# RoverWing-V1_5.net
KiCad netlist of a schematic drawn in EAGLE
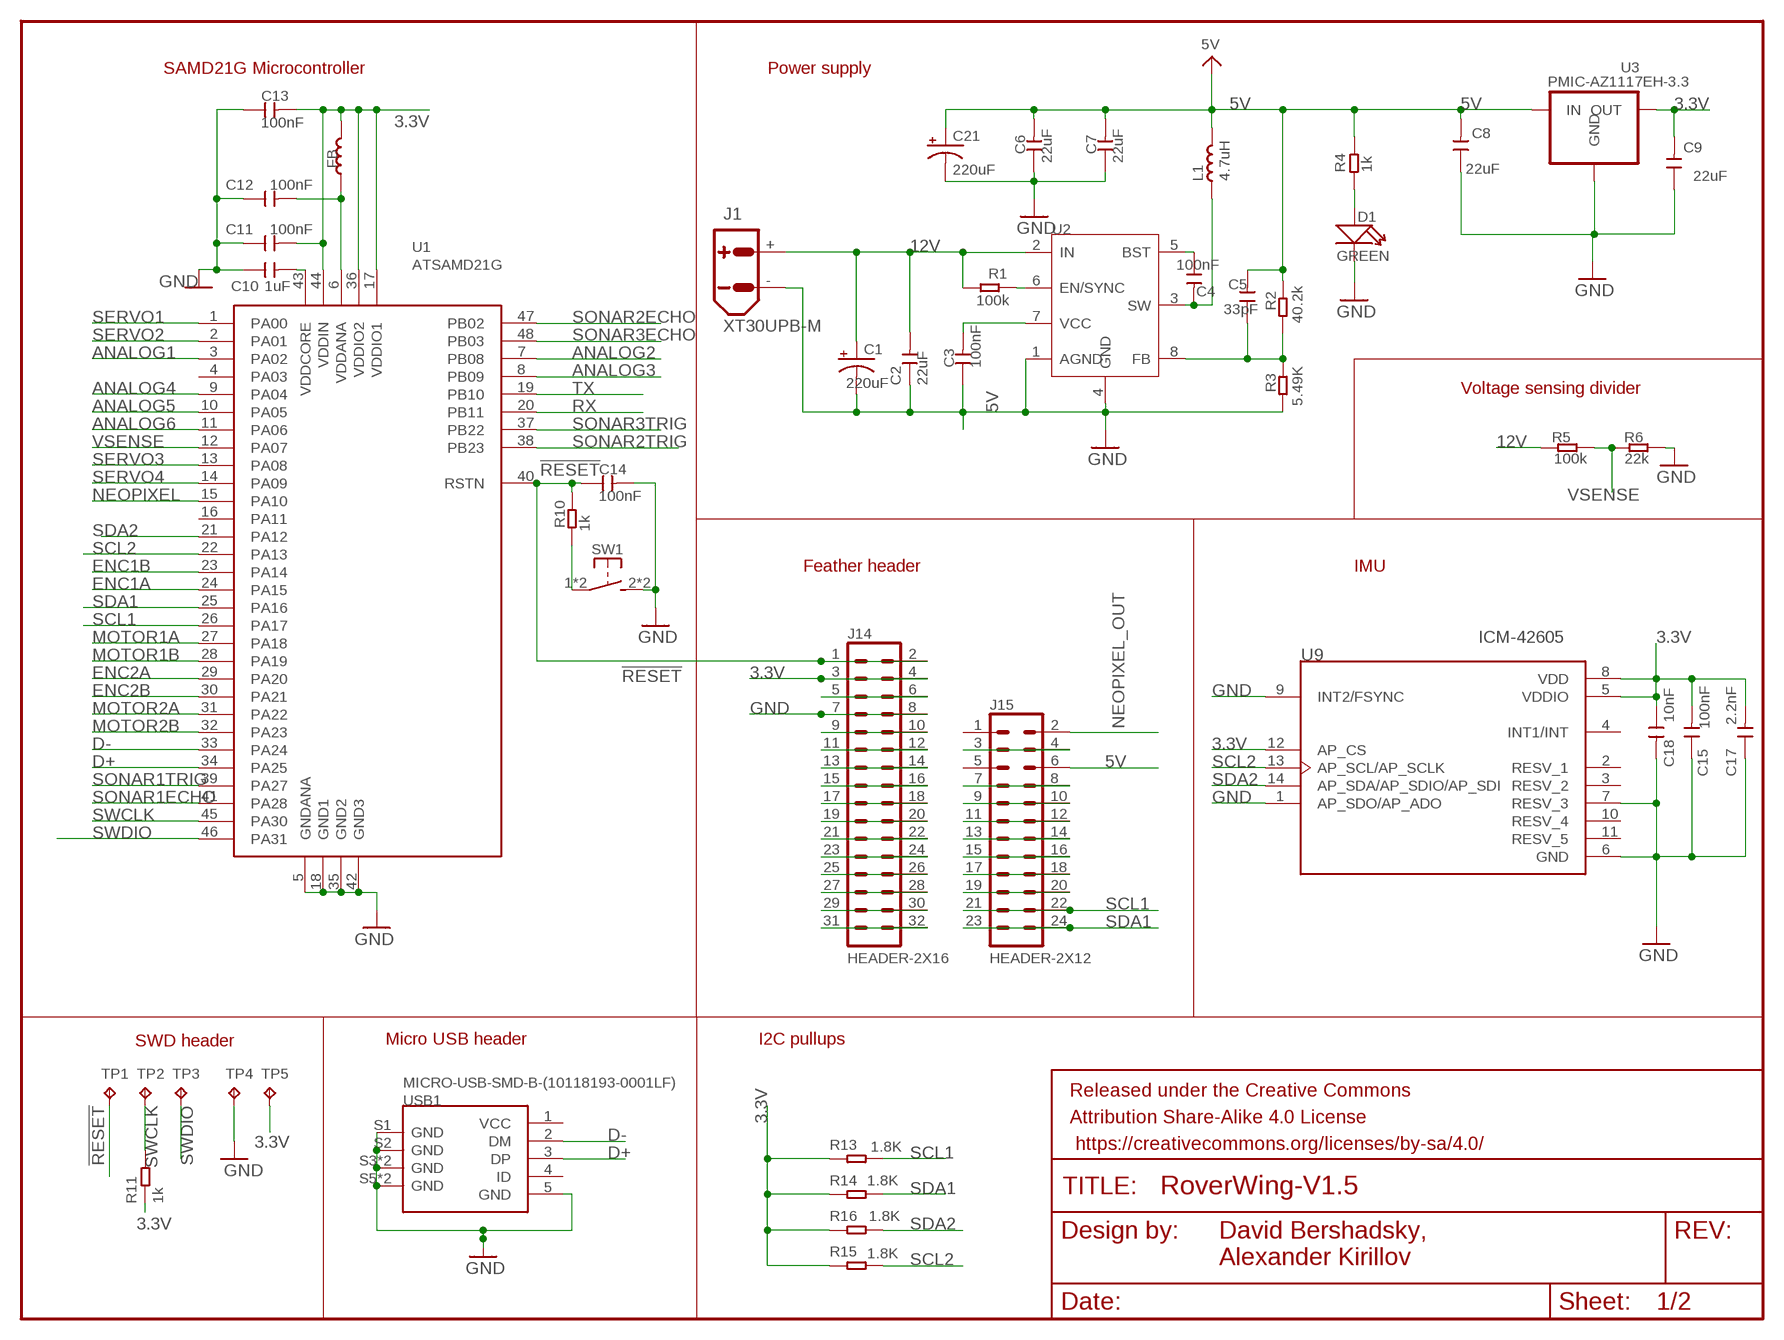
[diagram p0: schematic, sheet 1]
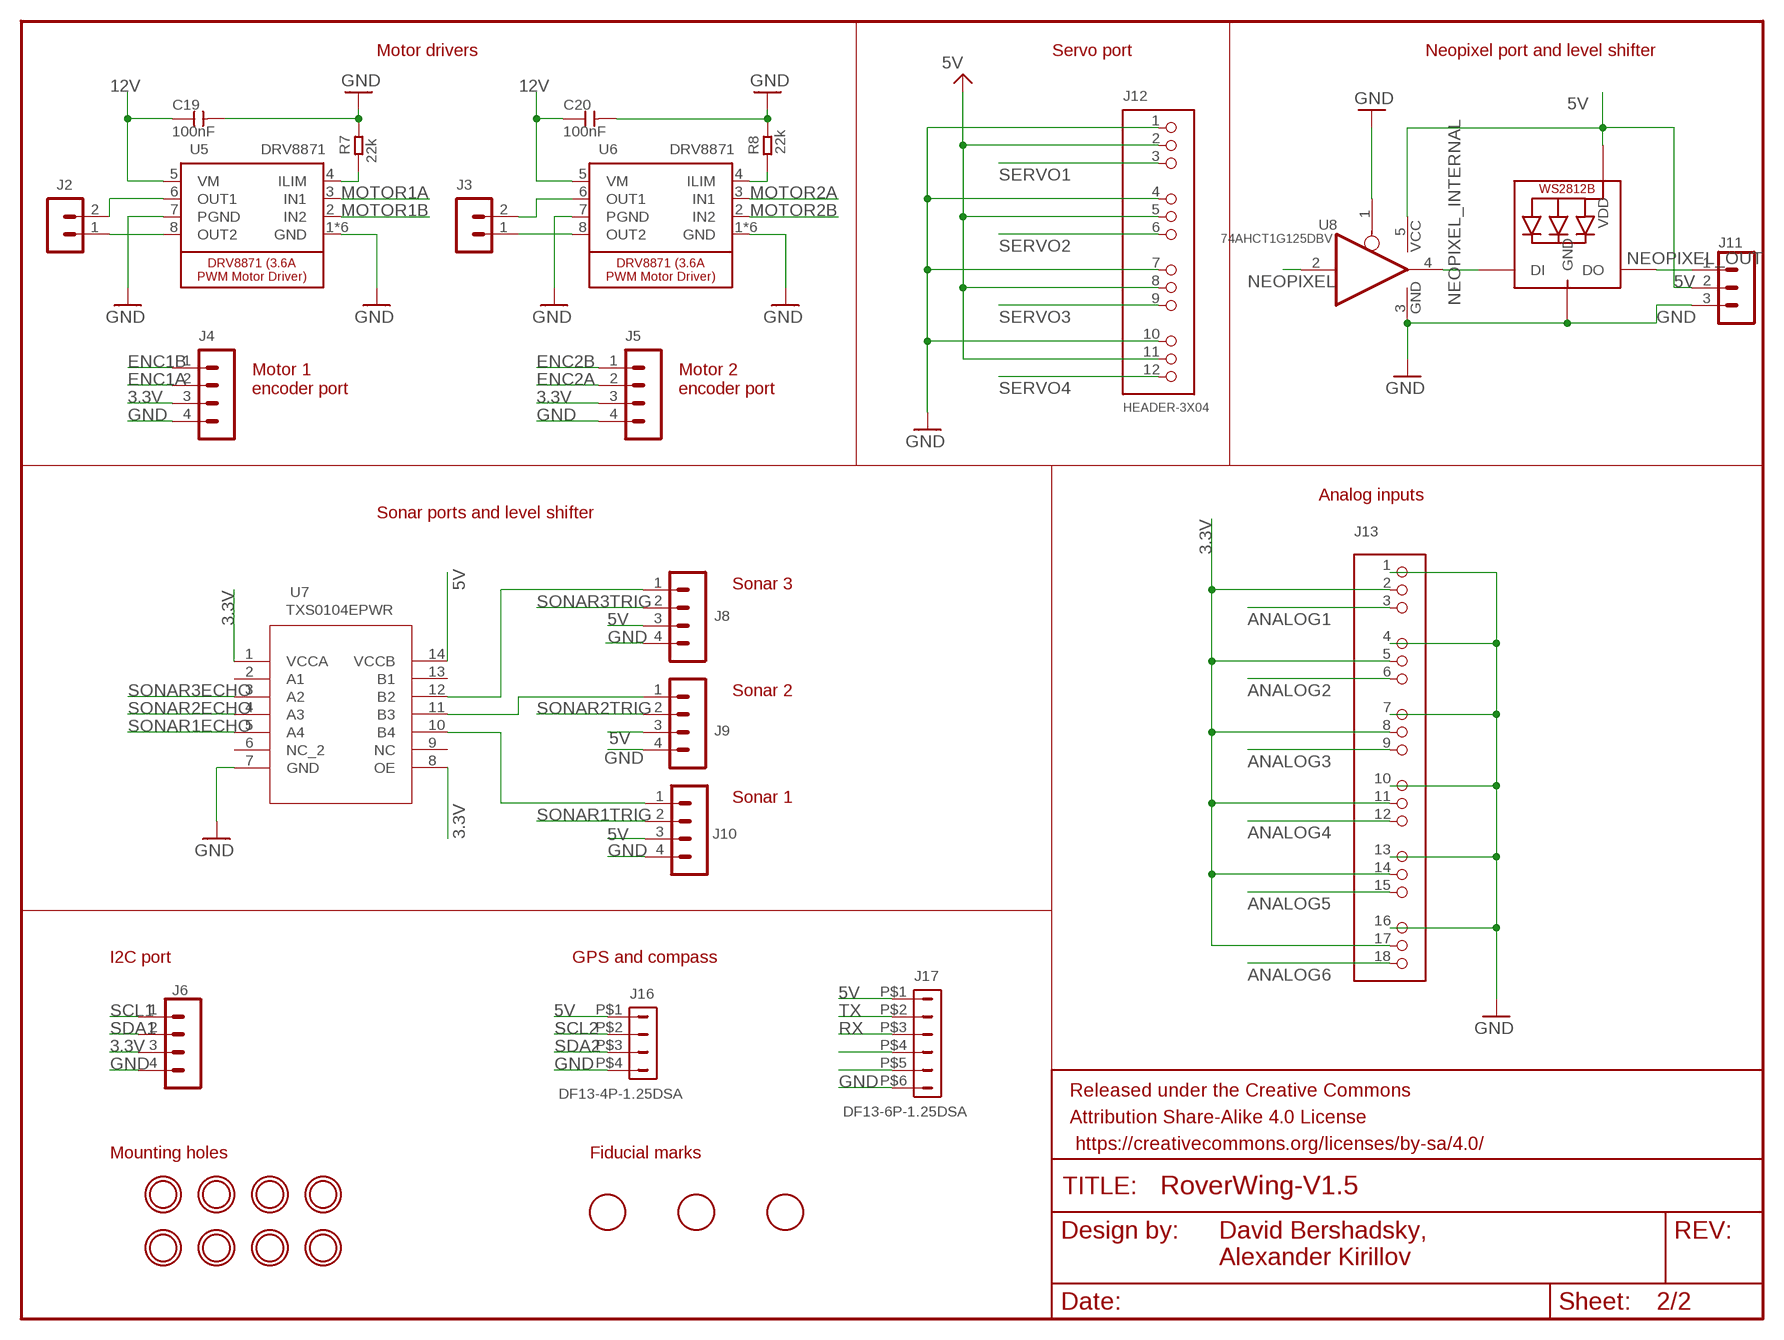
[diagram p1: schematic, sheet 2]

(export (version "E")
  (design (tool "Eeschema 10.0.6"))
  (components
    (comp (ref "C19")
      (value "100nF")
      (footprint "eagle-import:0805")
      (libsource (lib "eagle-import") (part "CAP-CERAMIC-SMD0805"))
    )
    (comp (ref "C20")
      (value "100nF")
      (footprint "eagle-import:0805")
      (libsource (lib "eagle-import") (part "CAP-CERAMIC-SMD0805"))
    )
    (comp (ref "D2")
      (value "WS2812B3535")
      (footprint "eagle-import:LED3535")
      (fields (field (name "MANUFACTURER") "Worldsemi") (field (name "PARTNO") "WS2812B-3535 "))
      (libsource (lib "eagle-import") (part "WS2812B3535"))
    )
    (comp (ref "FRAME1")
      (value "FRAME-LETTERNO_PACKAGE")
      (footprint "eagle-import:DUMMY")
      (libsource (lib "eagle-import") (part "FRAME-LETTERNO_PACKAGE"))
    )
    (comp (ref "J2")
      (value "HEADER-VH")
      (footprint "eagle-import:B2P-VH")
      (fields (field (name "PARTNO") "B2P-VH(LF)(SN)  "))
      (libsource (lib "eagle-import") (part "HEADER-VH"))
    )
    (comp (ref "J3")
      (value "HEADER-VH")
      (footprint "eagle-import:B2P-VH")
      (fields (field (name "PARTNO") "B2P-VH(LF)(SN)  "))
      (libsource (lib "eagle-import") (part "HEADER-VH"))
    )
    (comp (ref "J4")
      (value "HEADER-PH-4P")
      (footprint "eagle-import:B4B-PH-K")
      (fields (field (name "PARTNO") "B4B-PH-K-S(LF)(SN)"))
      (libsource (lib "eagle-import") (part "HEADER-PH-4P"))
    )
    (comp (ref "J5")
      (value "HEADER-PH-4P")
      (footprint "eagle-import:B4B-PH-K")
      (fields (field (name "PARTNO") "B4B-PH-K-S(LF)(SN)"))
      (libsource (lib "eagle-import") (part "HEADER-PH-4P"))
    )
    (comp (ref "J6")
      (value "HEADER-PH-4P")
      (footprint "eagle-import:B4B-PH-K")
      (fields (field (name "PARTNO") "B4B-PH-K-S(LF)(SN)"))
      (libsource (lib "eagle-import") (part "HEADER-PH-4P"))
    )
    (comp (ref "J8")
      (value "HEADER-PH-4P")
      (footprint "eagle-import:B4B-PH-K")
      (fields (field (name "PARTNO") "B4B-PH-K-S(LF)(SN)"))
      (libsource (lib "eagle-import") (part "HEADER-PH-4P"))
    )
    (comp (ref "J9")
      (value "HEADER-PH-4P")
      (footprint "eagle-import:B4B-PH-K")
      (fields (field (name "PARTNO") "B4B-PH-K-S(LF)(SN)"))
      (libsource (lib "eagle-import") (part "HEADER-PH-4P"))
    )
    (comp (ref "J10")
      (value "HEADER-PH-4P")
      (footprint "eagle-import:B4B-PH-K")
      (fields (field (name "PARTNO") "B4B-PH-K-S(LF)(SN)"))
      (libsource (lib "eagle-import") (part "HEADER-PH-4P"))
    )
    (comp (ref "J11")
      (value "HEADER-PH-3P")
      (footprint "eagle-import:B3B-PH-K")
      (fields (field (name "PARTNO") "B3B-PH-K-S(LF)(SN)"))
      (libsource (lib "eagle-import") (part "HEADER-PH-3P"))
    )
    (comp (ref "J12")
      (value "HEADER-3X04")
      (footprint "eagle-import:3X04")
      (libsource (lib "eagle-import") (part "HEADER-3X04"))
    )
    (comp (ref "J13")
      (value "HEADER-3X06\"")
      (footprint "eagle-import:3X06")
      (libsource (lib "eagle-import") (part "HEADER-3X06{dblquote}"))
    )
    (comp (ref "J16")
      (value "DF13-4P-1.25DSA")
      (footprint "eagle-import:DF13-4P-1.25DSA")
      (libsource (lib "eagle-import") (part "DF13-4P-1.25DSA"))
    )
    (comp (ref "J17")
      (value "DF13-6P-1.25DSA")
      (footprint "eagle-import:DF13-6P-1.25DSA")
      (libsource (lib "eagle-import") (part "DF13-6P-1.25DSA"))
    )
    (comp (ref "R7")
      (value "22k")
      (footprint "eagle-import:0805")
      (libsource (lib "eagle-import") (part "RES-SMD-0805"))
    )
    (comp (ref "R8")
      (value "22k")
      (footprint "eagle-import:0805")
      (libsource (lib "eagle-import") (part "RES-SMD-0805"))
    )
    (comp (ref "U$3")
      (value "MOUNTINGHOLE3.0_NPH")
      (footprint "eagle-import:MOUNTINGHOLE_3.0_NPH")
      (libsource (lib "eagle-import") (part "MOUNTINGHOLE3.0_NPH"))
    )
    (comp (ref "U$4")
      (value "MOUNTINGHOLE3.0_NPH")
      (footprint "eagle-import:MOUNTINGHOLE_3.0_NPH")
      (libsource (lib "eagle-import") (part "MOUNTINGHOLE3.0_NPH"))
    )
    (comp (ref "U$11")
      (value "FIDUCIAL")
      (footprint "eagle-import:FIDUCIAL_1MM")
      (libsource (lib "eagle-import") (part "FIDUCIAL"))
    )
    (comp (ref "U$13")
      (value "FIDUCIAL")
      (footprint "eagle-import:FIDUCIAL_1MM")
      (libsource (lib "eagle-import") (part "FIDUCIAL"))
    )
    (comp (ref "U$14")
      (value "MOUNTINGHOLE3.0_NPH")
      (footprint "eagle-import:MOUNTINGHOLE_3.0_NPH")
      (libsource (lib "eagle-import") (part "MOUNTINGHOLE3.0_NPH"))
    )
    (comp (ref "U$15")
      (value "MOUNTINGHOLE3.0_NPH")
      (footprint "eagle-import:MOUNTINGHOLE_3.0_NPH")
      (libsource (lib "eagle-import") (part "MOUNTINGHOLE3.0_NPH"))
    )
    (comp (ref "U$17")
      (value "FIDUCIAL")
      (footprint "eagle-import:FIDUCIAL_1MM")
      (libsource (lib "eagle-import") (part "FIDUCIAL"))
    )
    (comp (ref "U$24")
      (value "MOUNTINGHOLE3.0_NPH")
      (footprint "eagle-import:MOUNTINGHOLE_3.0_NPH")
      (libsource (lib "eagle-import") (part "MOUNTINGHOLE3.0_NPH"))
    )
    (comp (ref "U$25")
      (value "MOUNTINGHOLE3.0_NPH")
      (footprint "eagle-import:MOUNTINGHOLE_3.0_NPH")
      (libsource (lib "eagle-import") (part "MOUNTINGHOLE3.0_NPH"))
    )
    (comp (ref "U$26")
      (value "MOUNTINGHOLE3.0_NPH")
      (footprint "eagle-import:MOUNTINGHOLE_3.0_NPH")
      (libsource (lib "eagle-import") (part "MOUNTINGHOLE3.0_NPH"))
    )
    (comp (ref "U$27")
      (value "MOUNTINGHOLE3.0_NPH")
      (footprint "eagle-import:MOUNTINGHOLE_3.0_NPH")
      (libsource (lib "eagle-import") (part "MOUNTINGHOLE3.0_NPH"))
    )
    (comp (ref "U5")
      (value "DRV8871")
      (footprint "eagle-import:HSOP8")
      (fields (field (name "MANUFACTURER") "TEXAS INSTRUMENTS") (field (name "PARTNO") "DRV8871DDAR"))
      (libsource (lib "eagle-import") (part "DRV8871"))
    )
    (comp (ref "U6")
      (value "DRV8871")
      (footprint "eagle-import:HSOP8")
      (fields (field (name "MANUFACTURER") "TEXAS INSTRUMENTS") (field (name "PARTNO") "DRV8871DDAR"))
      (libsource (lib "eagle-import") (part "DRV8871"))
    )
    (comp (ref "U7")
      (value "TXS0104EPWR")
      (footprint "eagle-import:PW14")
      (fields (field (name "MANUFACTURER") "Texas Instruments"))
      (libsource (lib "eagle-import") (part "TXS0104EPWR"))
    )
    (comp (ref "U8")
      (value "74AHCT1G125DBV")
      (footprint "eagle-import:SOT23-5")
      (fields (field (name "PARTNO") "SN74AHCT1G125DBVR"))
      (libsource (lib "eagle-import") (part "741G125DBVAHCT"))
    )
    (comp (ref "C1")
      (value "220uF")
      (footprint "eagle-import:CAP-8X10.5")
      (libsource (lib "eagle-import") (part "CAP-POL-SMD-8X10.5"))
    )
    (comp (ref "C2")
      (value "22uF")
      (footprint "eagle-import:0805")
      (libsource (lib "eagle-import") (part "CAP-CERAMIC-SMD0805"))
    )
    (comp (ref "C3")
      (value "100nF")
      (footprint "eagle-import:0805")
      (libsource (lib "eagle-import") (part "CAP-CERAMIC-SMD0805"))
    )
    (comp (ref "C4")
      (value "100nF")
      (footprint "eagle-import:0805")
      (libsource (lib "eagle-import") (part "CAP-CERAMIC-SMD0805"))
    )
    (comp (ref "C5")
      (value "33pF")
      (footprint "eagle-import:0805")
      (libsource (lib "eagle-import") (part "CAP-CERAMIC-SMD0805"))
    )
    (comp (ref "C6")
      (value "22uF")
      (footprint "eagle-import:0805")
      (libsource (lib "eagle-import") (part "CAP-CERAMIC-SMD0805"))
    )
    (comp (ref "C7")
      (value "22uF")
      (footprint "eagle-import:0805")
      (libsource (lib "eagle-import") (part "CAP-CERAMIC-SMD0805"))
    )
    (comp (ref "C8")
      (value "22uF")
      (footprint "eagle-import:0805")
      (libsource (lib "eagle-import") (part "CAP-CERAMIC-SMD0805"))
    )
    (comp (ref "C9")
      (value "22uF")
      (footprint "eagle-import:0805")
      (libsource (lib "eagle-import") (part "CAP-CERAMIC-SMD0805"))
    )
    (comp (ref "C10")
      (value "1uF")
      (footprint "eagle-import:0805")
      (libsource (lib "eagle-import") (part "CAP-CERAMIC-SMD0805"))
    )
    (comp (ref "C11")
      (value "100nF")
      (footprint "eagle-import:0805")
      (libsource (lib "eagle-import") (part "CAP-CERAMIC-SMD0805"))
    )
    (comp (ref "C12")
      (value "100nF")
      (footprint "eagle-import:0805")
      (libsource (lib "eagle-import") (part "CAP-CERAMIC-SMD0805"))
    )
    (comp (ref "C13")
      (value "100nF")
      (footprint "eagle-import:0805")
      (libsource (lib "eagle-import") (part "CAP-CERAMIC-SMD0805"))
    )
    (comp (ref "C14")
      (value "100nF")
      (footprint "eagle-import:0805")
      (libsource (lib "eagle-import") (part "CAP-CERAMIC-SMD0805"))
    )
    (comp (ref "C15")
      (value "100nF")
      (footprint "eagle-import:0805")
      (libsource (lib "eagle-import") (part "CAP-CERAMIC-SMD0805"))
    )
    (comp (ref "C17")
      (value "2.2nF")
      (footprint "eagle-import:0805")
      (libsource (lib "eagle-import") (part "CAP-CERAMIC-SMD0805"))
    )
    (comp (ref "C18")
      (value "10nF")
      (footprint "eagle-import:0805")
      (libsource (lib "eagle-import") (part "CAP-CERAMIC-SMD0805"))
    )
    (comp (ref "C21")
      (value "220uF")
      (footprint "eagle-import:CAP-8X10.5")
      (libsource (lib "eagle-import") (part "CAP-POL-SMD-8X10.5"))
    )
    (comp (ref "D1")
      (value "GREEN")
      (footprint "eagle-import:LED-0805")
      (libsource (lib "eagle-import") (part "SMD-LED-0805"))
    )
    (comp (ref "FB")
      (value "330R-1500MA")
      (footprint "eagle-import:0805")
      (fields (field (name "PARTNO") "BLM21PG331SN1D"))
      (libsource (lib "eagle-import") (part "SMD-FERRITE-BEAD-330R-1500MA(0805)"))
    )
    (comp (ref "FRAME2")
      (value "FRAME-LETTERNO_PACKAGE")
      (footprint "eagle-import:DUMMY")
      (libsource (lib "eagle-import") (part "FRAME-LETTERNO_PACKAGE"))
    )
    (comp (ref "J1")
      (value "XT30UPB-M")
      (footprint "eagle-import:XT30UPB-M")
      (libsource (lib "eagle-import") (part "XT30UPB-M"))
    )
    (comp (ref "J14")
      (value "HEADER-2X16")
      (footprint "eagle-import:2X16")
      (libsource (lib "eagle-import") (part "HEADER-2X16"))
    )
    (comp (ref "J15")
      (value "HEADER-2X12")
      (footprint "eagle-import:2X12")
      (libsource (lib "eagle-import") (part "HEADER-2X12"))
    )
    (comp (ref "L1")
      (value "4.7uH")
      (footprint "eagle-import:IND_TDK_7.1X6.5")
      (fields (field (name "MANUFACTURER") "TDK") (field (name "PARTNO") "SPM6530T-4R7M "))
      (libsource (lib "eagle-import") (part "IND-TDK-SPM6530T"))
    )
    (comp (ref "R1")
      (value "100k")
      (footprint "eagle-import:0805")
      (libsource (lib "eagle-import") (part "RES-SMD-0805"))
    )
    (comp (ref "R2")
      (value "40.2k")
      (footprint "eagle-import:0805")
      (libsource (lib "eagle-import") (part "RES-SMD-0805"))
    )
    (comp (ref "R3")
      (value "5.49K")
      (footprint "eagle-import:0805")
      (libsource (lib "eagle-import") (part "RES-SMD-0805"))
    )
    (comp (ref "R4")
      (value "1k")
      (footprint "eagle-import:0805")
      (libsource (lib "eagle-import") (part "RES-SMD-0805"))
    )
    (comp (ref "R5")
      (value "100k")
      (footprint "eagle-import:0805")
      (libsource (lib "eagle-import") (part "RES-SMD-0805"))
    )
    (comp (ref "R6")
      (value "22k")
      (footprint "eagle-import:0805")
      (libsource (lib "eagle-import") (part "RES-SMD-0805"))
    )
    (comp (ref "R10")
      (value "1k")
      (footprint "eagle-import:0805")
      (libsource (lib "eagle-import") (part "RES-SMD-0805"))
    )
    (comp (ref "R11")
      (value "1k")
      (footprint "eagle-import:0805")
      (libsource (lib "eagle-import") (part "RES-SMD-0805"))
    )
    (comp (ref "R13")
      (value "1.8K")
      (footprint "eagle-import:R0603")
      (fields (field (name "MPN") "RC0603FR-071K8L"))
      (libsource (lib "eagle-import") (part "SMD-RES-1.8K-1%-1/10W(0603)"))
    )
    (comp (ref "R14")
      (value "1.8K")
      (footprint "eagle-import:R0603")
      (fields (field (name "MPN") "RC0603FR-071K8L"))
      (libsource (lib "eagle-import") (part "SMD-RES-1.8K-1%-1/10W(0603)"))
    )
    (comp (ref "R15")
      (value "1.8K")
      (footprint "eagle-import:R0603")
      (fields (field (name "MPN") "RC0603FR-071K8L"))
      (libsource (lib "eagle-import") (part "SMD-RES-1.8K-1%-1/10W(0603)"))
    )
    (comp (ref "R16")
      (value "1.8K")
      (footprint "eagle-import:R0603")
      (fields (field (name "MPN") "RC0603FR-071K8L"))
      (libsource (lib "eagle-import") (part "SMD-RES-1.8K-1%-1/10W(0603)"))
    )
    (comp (ref "SW1")
      (value "SW-TACTILE-4.5X4.5_SMD")
      (footprint "eagle-import:TL3305")
      (fields (field (name "MANUFACTURER") "BRIGHT") (field (name "PARTNO") "TSA453G38-250 "))
      (libsource (lib "eagle-import") (part "SW-TACTILE-4.5X4.5_SMD"))
    )
    (comp (ref "TP1")
      (value "TPTP15R")
      (footprint "eagle-import:TP15R")
      (libsource (lib "eagle-import") (part "TPTP15R"))
    )
    (comp (ref "TP2")
      (value "TPTP15R")
      (footprint "eagle-import:TP15R")
      (libsource (lib "eagle-import") (part "TPTP15R"))
    )
    (comp (ref "TP3")
      (value "TPTP15R")
      (footprint "eagle-import:TP15R")
      (libsource (lib "eagle-import") (part "TPTP15R"))
    )
    (comp (ref "TP4")
      (value "TPTP15R")
      (footprint "eagle-import:TP15R")
      (libsource (lib "eagle-import") (part "TPTP15R"))
    )
    (comp (ref "TP5")
      (value "TPTP15R")
      (footprint "eagle-import:TP15R")
      (libsource (lib "eagle-import") (part "TPTP15R"))
    )
    (comp (ref "U1")
      (value "ATSAMD21G")
      (footprint "eagle-import:TQFP-48-EDITED")
      (fields (field (name "MANUFACTURER") "Microchip Technology") (field (name "PARTNO") "ATSAMD21G18A-AU"))
      (libsource (lib "eagle-import") (part "ATSAMD21G"))
    )
    (comp (ref "U2")
      (value "MP2225")
      (footprint "eagle-import:SOT-23-8")
      (fields (field (name "MANUFACTURER") "Monolithic Power Systems") (field (name "PARTNO") "MP2225GJ"))
      (libsource (lib "eagle-import") (part "PMIC-MP2225"))
    )
    (comp (ref "U3")
      (value "PMIC-AZ1117EH-3.3")
      (footprint "eagle-import:SOT223")
      (fields (field (name "PARTNO") "AZ1117EH-3.3TRG1"))
      (libsource (lib "eagle-import") (part "PMIC-AZ1117EH-3.3"))
    )
    (comp (ref "U9")
      (value "ICM-42605")
      (footprint "eagle-import:PQFN50P300X250X97-14N")
      (fields (field (name "DIGI-KEY_PART_NUMBER") "1428-1152-1-ND") (field (name "MF") "TDK InvenSense"))
      (libsource (lib "eagle-import") (part "ICM-42605"))
    )
    (comp (ref "USB1")
      (value "MICRO-USB-SMD-B-(10118193-0001LF)")
      (footprint "eagle-import:MICRO-USB5+6P-SMD-0.65-B")
      (fields (field (name "MANUFACTURER") "Amphenol ICC") (field (name "PARTNO") "10118193-0001LF"))
      (libsource (lib "eagle-import") (part "MICRO-USB-SMD-B-(10118193-0001LF)"))
    )
  )
  (nets
    (net (code "1") (name "3.3V") (class "Default")
      (node (ref "C11") (pin "2") (pinfunction "2_2") (pintype "passive"))
      (node (ref "C13") (pin "2") (pinfunction "2_2") (pintype "passive"))
      (node (ref "C15") (pin "2") (pinfunction "2_2") (pintype "passive"))
      (node (ref "C17") (pin "2") (pinfunction "2_2") (pintype "passive"))
      (node (ref "C18") (pin "1") (pinfunction "1_1") (pintype "passive"))
      (node (ref "C9") (pin "2") (pinfunction "2_2") (pintype "passive"))
      (node (ref "FB") (pin "2") (pinfunction "2_2") (pintype "passive"))
      (node (ref "J13") (pin "11") (pinfunction "11_11") (pintype "passive"))
      (node (ref "J13") (pin "14") (pinfunction "14_14") (pintype "passive"))
      (node (ref "J13") (pin "17") (pinfunction "17_17") (pintype "passive"))
      (node (ref "J13") (pin "2") (pinfunction "2_2") (pintype "passive"))
      (node (ref "J13") (pin "5") (pinfunction "5_5") (pintype "passive"))
      (node (ref "J13") (pin "8") (pinfunction "8_8") (pintype "passive"))
      (node (ref "J14") (pin "3") (pinfunction "3_3") (pintype "passive"))
      (node (ref "J14") (pin "4") (pinfunction "4_4") (pintype "passive"))
      (node (ref "J4") (pin "3") (pinfunction "3_3") (pintype "passive"))
      (node (ref "J5") (pin "3") (pinfunction "3_3") (pintype "passive"))
      (node (ref "J6") (pin "3") (pinfunction "3_3") (pintype "passive"))
      (node (ref "R11") (pin "1") (pinfunction "1_1") (pintype "passive"))
      (node (ref "R13") (pin "1") (pinfunction "1_1") (pintype "passive"))
      (node (ref "R14") (pin "1") (pinfunction "1_1") (pintype "passive"))
      (node (ref "R15") (pin "1") (pinfunction "1_1") (pintype "passive"))
      (node (ref "R16") (pin "1") (pinfunction "1_1") (pintype "passive"))
      (node (ref "TP5") (pin "TP") (pinfunction "TP_TP") (pintype "input"))
      (node (ref "U1") (pin "17") (pinfunction "VDDIO1_17") (pintype "power_in"))
      (node (ref "U1") (pin "36") (pinfunction "VDDIO2_36") (pintype "power_in"))
      (node (ref "U1") (pin "44") (pinfunction "VDDIN_44") (pintype "power_in"))
      (node (ref "U3") (pin "2") (pinfunction "OUT_2") (pintype "output"))
      (node (ref "U3") (pin "4") (pinfunction "OUT_4") (pintype "output"))
      (node (ref "U7") (pin "1") (pinfunction "VCCA_1") (pintype "power_in"))
      (node (ref "U7") (pin "8") (pinfunction "OE_8") (pintype "output"))
      (node (ref "U9") (pin "12") (pinfunction "AP_CS_12") (pintype "input"))
      (node (ref "U9") (pin "5") (pinfunction "VDDIO_5") (pintype "power_in"))
      (node (ref "U9") (pin "8") (pinfunction "VDD_8") (pintype "power_in"))
    )
    (net (code "2") (name "5V") (class "Default")
      (node (ref "C21") (pin "+") (pinfunction "+_+") (pintype "passive"))
      (node (ref "C5") (pin "2") (pinfunction "2_2") (pintype "passive"))
      (node (ref "C6") (pin "2") (pinfunction "2_2") (pintype "passive"))
      (node (ref "C7") (pin "2") (pinfunction "2_2") (pintype "passive"))
      (node (ref "C8") (pin "2") (pinfunction "2_2") (pintype "passive"))
      (node (ref "D2") (pin "3") (pinfunction "VDD_3") (pintype "power_in"))
      (node (ref "J10") (pin "3") (pinfunction "3_3") (pintype "passive"))
      (node (ref "J11") (pin "2") (pinfunction "2_2") (pintype "passive"))
      (node (ref "J12") (pin "11") (pinfunction "11_11") (pintype "passive"))
      (node (ref "J12") (pin "2") (pinfunction "2_2") (pintype "passive"))
      (node (ref "J12") (pin "5") (pinfunction "5_5") (pintype "passive"))
      (node (ref "J12") (pin "8") (pinfunction "8_8") (pintype "passive"))
      (node (ref "J15") (pin "6") (pinfunction "6_6") (pintype "passive"))
      (node (ref "J16") (pin "P$1") (pinfunction "1_P$1") (pintype "passive"))
      (node (ref "J17") (pin "P$1") (pinfunction "1_P$1") (pintype "passive"))
      (node (ref "J8") (pin "3") (pinfunction "3_3") (pintype "passive"))
      (node (ref "J9") (pin "3") (pinfunction "3_3") (pintype "passive"))
      (node (ref "L1") (pin "2") (pinfunction "2_2") (pintype "passive"))
      (node (ref "R2") (pin "1") (pinfunction "1_1") (pintype "passive"))
      (node (ref "R4") (pin "2") (pinfunction "2_2") (pintype "passive"))
      (node (ref "U3") (pin "3") (pinfunction "IN_3") (pintype "input"))
      (node (ref "U7") (pin "14") (pinfunction "VCCB_14") (pintype "power_in"))
      (node (ref "U8") (pin "5") (pinfunction "VCC_5") (pintype "power_in"))
    )
    (net (code "3") (name "12V") (class "Default")
      (node (ref "C1") (pin "+") (pinfunction "+_+") (pintype "passive"))
      (node (ref "C19") (pin "1") (pinfunction "1_1") (pintype "passive"))
      (node (ref "C2") (pin "2") (pinfunction "2_2") (pintype "passive"))
      (node (ref "C20") (pin "1") (pinfunction "1_1") (pintype "passive"))
      (node (ref "J1") (pin "+") (pinfunction "+_+") (pintype "power_in"))
      (node (ref "R1") (pin "2") (pinfunction "2_2") (pintype "passive"))
      (node (ref "R5") (pin "2") (pinfunction "2_2") (pintype "passive"))
      (node (ref "U2") (pin "2") (pinfunction "IN_2") (pintype "bidirectional"))
      (node (ref "U5") (pin "5") (pinfunction "VM_5") (pintype "power_in"))
      (node (ref "U6") (pin "5") (pinfunction "VM_5") (pintype "power_in"))
    )
    (net (code "4") (name "ANALOG1") (class "Default")
      (node (ref "J13") (pin "3") (pinfunction "3_3") (pintype "passive"))
      (node (ref "U1") (pin "3") (pinfunction "PA02_3") (pintype "bidirectional"))
    )
    (net (code "5") (name "ANALOG2") (class "Default")
      (node (ref "J13") (pin "6") (pinfunction "6_6") (pintype "passive"))
      (node (ref "U1") (pin "7") (pinfunction "PB08_7") (pintype "bidirectional"))
    )
    (net (code "6") (name "ANALOG3") (class "Default")
      (node (ref "J13") (pin "9") (pinfunction "9_9") (pintype "passive"))
      (node (ref "U1") (pin "8") (pinfunction "PB09_8") (pintype "bidirectional"))
    )
    (net (code "7") (name "ANALOG4") (class "Default")
      (node (ref "J13") (pin "12") (pinfunction "12_12") (pintype "passive"))
      (node (ref "U1") (pin "9") (pinfunction "PA04_9") (pintype "bidirectional"))
    )
    (net (code "8") (name "ANALOG5") (class "Default")
      (node (ref "J13") (pin "15") (pinfunction "15_15") (pintype "passive"))
      (node (ref "U1") (pin "10") (pinfunction "PA05_10") (pintype "bidirectional"))
    )
    (net (code "9") (name "ANALOG6") (class "Default")
      (node (ref "J13") (pin "18") (pinfunction "18_18") (pintype "passive"))
      (node (ref "U1") (pin "11") (pinfunction "PA06_11") (pintype "bidirectional"))
    )
    (net (code "10") (name "D+") (class "Default")
      (node (ref "U1") (pin "34") (pinfunction "PA25_34") (pintype "bidirectional"))
      (node (ref "USB1") (pin "3") (pinfunction "DP_3") (pintype "bidirectional"))
    )
    (net (code "11") (name "D-") (class "Default")
      (node (ref "U1") (pin "33") (pinfunction "PA24_33") (pintype "bidirectional"))
      (node (ref "USB1") (pin "2") (pinfunction "DM_2") (pintype "bidirectional"))
    )
    (net (code "12") (name "ENC1A") (class "Default")
      (node (ref "J4") (pin "2") (pinfunction "2_2") (pintype "passive"))
      (node (ref "U1") (pin "24") (pinfunction "PA15_24") (pintype "bidirectional"))
    )
    (net (code "13") (name "ENC1B") (class "Default")
      (node (ref "J4") (pin "1") (pinfunction "1_1") (pintype "passive"))
      (node (ref "U1") (pin "23") (pinfunction "PA14_23") (pintype "bidirectional"))
    )
    (net (code "14") (name "ENC2A") (class "Default")
      (node (ref "J5") (pin "2") (pinfunction "2_2") (pintype "passive"))
      (node (ref "U1") (pin "29") (pinfunction "PA20_29") (pintype "bidirectional"))
    )
    (net (code "15") (name "ENC2B") (class "Default")
      (node (ref "J5") (pin "1") (pinfunction "1_1") (pintype "passive"))
      (node (ref "U1") (pin "30") (pinfunction "PA21_30") (pintype "bidirectional"))
    )
    (net (code "16") (name "GND") (class "Default")
      (node (ref "C1") (pin "-") (pinfunction "-_-") (pintype "passive"))
      (node (ref "C10") (pin "1") (pinfunction "1_1") (pintype "passive"))
      (node (ref "C11") (pin "1") (pinfunction "1_1") (pintype "passive"))
      (node (ref "C12") (pin "1") (pinfunction "1_1") (pintype "passive"))
      (node (ref "C13") (pin "1") (pinfunction "1_1") (pintype "passive"))
      (node (ref "C14") (pin "2") (pinfunction "2_2") (pintype "passive"))
      (node (ref "C15") (pin "1") (pinfunction "1_1") (pintype "passive"))
      (node (ref "C17") (pin "1") (pinfunction "1_1") (pintype "passive"))
      (node (ref "C18") (pin "2") (pinfunction "2_2") (pintype "passive"))
      (node (ref "C19") (pin "2") (pinfunction "2_2") (pintype "passive"))
      (node (ref "C2") (pin "1") (pinfunction "1_1") (pintype "passive"))
      (node (ref "C20") (pin "2") (pinfunction "2_2") (pintype "passive"))
      (node (ref "C21") (pin "-") (pinfunction "-_-") (pintype "passive"))
      (node (ref "C3") (pin "1") (pinfunction "1_1") (pintype "passive"))
      (node (ref "C6") (pin "1") (pinfunction "1_1") (pintype "passive"))
      (node (ref "C7") (pin "1") (pinfunction "1_1") (pintype "passive"))
      (node (ref "C8") (pin "1") (pinfunction "1_1") (pintype "passive"))
      (node (ref "C9") (pin "1") (pinfunction "1_1") (pintype "passive"))
      (node (ref "D1") (pin "-") (pinfunction "-_-") (pintype "passive"))
      (node (ref "D2") (pin "1") (pinfunction "GND_1") (pintype "power_in"))
      (node (ref "J1") (pin "-") (pinfunction "-_-") (pintype "power_in"))
      (node (ref "J10") (pin "4") (pinfunction "4_4") (pintype "passive"))
      (node (ref "J11") (pin "3") (pinfunction "3_3") (pintype "passive"))
      (node (ref "J12") (pin "1") (pinfunction "1_1") (pintype "passive"))
      (node (ref "J12") (pin "10") (pinfunction "10_10") (pintype "passive"))
      (node (ref "J12") (pin "4") (pinfunction "4_4") (pintype "passive"))
      (node (ref "J12") (pin "7") (pinfunction "7_7") (pintype "passive"))
      (node (ref "J13") (pin "1") (pinfunction "1_1") (pintype "passive"))
      (node (ref "J13") (pin "10") (pinfunction "10_10") (pintype "passive"))
      (node (ref "J13") (pin "13") (pinfunction "13_13") (pintype "passive"))
      (node (ref "J13") (pin "16") (pinfunction "16_16") (pintype "passive"))
      (node (ref "J13") (pin "4") (pinfunction "4_4") (pintype "passive"))
      (node (ref "J13") (pin "7") (pinfunction "7_7") (pintype "passive"))
      (node (ref "J14") (pin "7") (pinfunction "7_7") (pintype "passive"))
      (node (ref "J14") (pin "8") (pinfunction "8_8") (pintype "passive"))
      (node (ref "J16") (pin "P$4") (pinfunction "4_P$4") (pintype "passive"))
      (node (ref "J17") (pin "P$6") (pinfunction "6_P$6") (pintype "passive"))
      (node (ref "J4") (pin "4") (pinfunction "4_4") (pintype "passive"))
      (node (ref "J5") (pin "4") (pinfunction "4_4") (pintype "passive"))
      (node (ref "J6") (pin "4") (pinfunction "4_4") (pintype "passive"))
      (node (ref "J8") (pin "4") (pinfunction "4_4") (pintype "passive"))
      (node (ref "J9") (pin "4") (pinfunction "4_4") (pintype "passive"))
      (node (ref "R3") (pin "2") (pinfunction "2_2") (pintype "passive"))
      (node (ref "R6") (pin "2") (pinfunction "2_2") (pintype "passive"))
      (node (ref "R7") (pin "2") (pinfunction "2_2") (pintype "passive"))
      (node (ref "R8") (pin "2") (pinfunction "2_2") (pintype "passive"))
      (node (ref "SW1") (pin "2") (pinfunction "S1_2") (pintype "passive"))
      (node (ref "SW1") (pin "3") (pinfunction "S1_3") (pintype "passive"))
      (node (ref "TP4") (pin "TP") (pinfunction "TP_TP") (pintype "input"))
      (node (ref "U1") (pin "18") (pinfunction "GND1_18") (pintype "power_in"))
      (node (ref "U1") (pin "35") (pinfunction "GND2_35") (pintype "power_in"))
      (node (ref "U1") (pin "42") (pinfunction "GND3_42") (pintype "power_in"))
      (node (ref "U1") (pin "5") (pinfunction "GNDANA_5") (pintype "power_in"))
      (node (ref "U2") (pin "1") (pinfunction "AGND_1") (pintype "bidirectional"))
      (node (ref "U2") (pin "4") (pinfunction "GND_4") (pintype "bidirectional"))
      (node (ref "U3") (pin "1") (pinfunction "GND_1") (pintype "power_in"))
      (node (ref "U5") (pin "1") (pinfunction "GND_1") (pintype "power_in"))
      (node (ref "U5") (pin "7") (pinfunction "PGND_7") (pintype "power_in"))
      (node (ref "U5") (pin "GND") (pinfunction "GND_GND") (pintype "power_in"))
      (node (ref "U5") (pin "P$1") (pinfunction "GND_P$1") (pintype "power_in"))
      (node (ref "U5") (pin "P$2") (pinfunction "GND_P$2") (pintype "power_in"))
      (node (ref "U5") (pin "P$3") (pinfunction "GND_P$3") (pintype "power_in"))
      (node (ref "U5") (pin "P$4") (pinfunction "GND_P$4") (pintype "power_in"))
      (node (ref "U6") (pin "1") (pinfunction "GND_1") (pintype "power_in"))
      (node (ref "U6") (pin "7") (pinfunction "PGND_7") (pintype "power_in"))
      (node (ref "U6") (pin "GND") (pinfunction "GND_GND") (pintype "power_in"))
      (node (ref "U6") (pin "P$1") (pinfunction "GND_P$1") (pintype "power_in"))
      (node (ref "U6") (pin "P$2") (pinfunction "GND_P$2") (pintype "power_in"))
      (node (ref "U6") (pin "P$3") (pinfunction "GND_P$3") (pintype "power_in"))
      (node (ref "U6") (pin "P$4") (pinfunction "GND_P$4") (pintype "power_in"))
      (node (ref "U7") (pin "7") (pinfunction "GND_7") (pintype "power_in"))
      (node (ref "U8") (pin "1") (pinfunction "OE_1") (pintype "input"))
      (node (ref "U8") (pin "3") (pinfunction "GND_3") (pintype "power_in"))
      (node (ref "U9") (pin "1") (pinfunction "AP_SDO/AP_ADO_1") (pintype "output"))
      (node (ref "U9") (pin "6") (pinfunction "GND_6") (pintype "power_in"))
      (node (ref "U9") (pin "7") (pinfunction "RESV_3_7") (pintype "bidirectional"))
      (node (ref "U9") (pin "9") (pinfunction "INT2/FSYNC_9") (pintype "bidirectional"))
      (node (ref "USB1") (pin "5") (pinfunction "GND_5") (pintype "bidirectional"))
      (node (ref "USB1") (pin "S1") (pinfunction "GND_S1") (pintype "bidirectional"))
      (node (ref "USB1") (pin "S2") (pinfunction "GND_S2") (pintype "bidirectional"))
      (node (ref "USB1") (pin "S3") (pinfunction "GND_S3") (pintype "bidirectional"))
      (node (ref "USB1") (pin "S4") (pinfunction "GND_S4") (pintype "bidirectional"))
      (node (ref "USB1") (pin "S5") (pinfunction "GND_S5") (pintype "bidirectional"))
      (node (ref "USB1") (pin "S6") (pinfunction "GND_S6") (pintype "bidirectional"))
    )
    (net (code "17") (name "MOTOR1A") (class "Default")
      (node (ref "U1") (pin "27") (pinfunction "PA18_27") (pintype "bidirectional"))
      (node (ref "U5") (pin "3") (pinfunction "IN1_3") (pintype "input"))
    )
    (net (code "18") (name "MOTOR1B") (class "Default")
      (node (ref "U1") (pin "28") (pinfunction "PA19_28") (pintype "bidirectional"))
      (node (ref "U5") (pin "2") (pinfunction "IN2_2") (pintype "input"))
    )
    (net (code "19") (name "MOTOR2A") (class "Default")
      (node (ref "U1") (pin "31") (pinfunction "PA22_31") (pintype "bidirectional"))
      (node (ref "U6") (pin "3") (pinfunction "IN1_3") (pintype "input"))
    )
    (net (code "20") (name "MOTOR2B") (class "Default")
      (node (ref "U1") (pin "32") (pinfunction "PA23_32") (pintype "bidirectional"))
      (node (ref "U6") (pin "2") (pinfunction "IN2_2") (pintype "input"))
    )
    (net (code "21") (name "NEOPIXEL") (class "Default")
      (node (ref "U1") (pin "15") (pinfunction "PA10_15") (pintype "bidirectional"))
      (node (ref "U8") (pin "2") (pinfunction "I_2") (pintype "input"))
    )
    (net (code "22") (name "NEOPIXEL_INTERNAL") (class "Default")
      (node (ref "D2") (pin "2") (pinfunction "DI_2") (pintype "input"))
      (node (ref "U8") (pin "4") (pinfunction "O_4") (pintype "tri_state"))
    )
    (net (code "23") (name "NEOPIXEL_OUT") (class "Default")
      (node (ref "D2") (pin "4") (pinfunction "DO_4") (pintype "output"))
      (node (ref "J11") (pin "1") (pinfunction "1_1") (pintype "passive"))
      (node (ref "J15") (pin "2") (pinfunction "2_2") (pintype "passive"))
    )
    (net (code "24") (name "Net-(D1-Pad+)") (class "Default")
      (node (ref "D1") (pin "+") (pinfunction "+_+") (pintype "passive"))
      (node (ref "R4") (pin "1") (pinfunction "1_1") (pintype "passive"))
    )
    (net (code "25") (name "Net-(J14-Pad5)") (class "Default")
      (node (ref "J14") (pin "5") (pinfunction "5_5") (pintype "passive"))
      (node (ref "J14") (pin "6") (pinfunction "6_6") (pintype "passive"))
    )
    (net (code "26") (name "Net-(J14-Pad10)") (class "Default")
      (node (ref "J14") (pin "10") (pinfunction "10_10") (pintype "passive"))
      (node (ref "J14") (pin "9") (pinfunction "9_9") (pintype "passive"))
    )
    (net (code "27") (name "Net-(J14-Pad11)") (class "Default")
      (node (ref "J14") (pin "11") (pinfunction "11_11") (pintype "passive"))
      (node (ref "J14") (pin "12") (pinfunction "12_12") (pintype "passive"))
    )
    (net (code "28") (name "Net-(J14-Pad13)") (class "Default")
      (node (ref "J14") (pin "13") (pinfunction "13_13") (pintype "passive"))
      (node (ref "J14") (pin "14") (pinfunction "14_14") (pintype "passive"))
    )
    (net (code "29") (name "Net-(J14-Pad15)") (class "Default")
      (node (ref "J14") (pin "15") (pinfunction "15_15") (pintype "passive"))
      (node (ref "J14") (pin "16") (pinfunction "16_16") (pintype "passive"))
    )
    (net (code "30") (name "Net-(J14-Pad17)") (class "Default")
      (node (ref "J14") (pin "17") (pinfunction "17_17") (pintype "passive"))
      (node (ref "J14") (pin "18") (pinfunction "18_18") (pintype "passive"))
    )
    (net (code "31") (name "Net-(J14-Pad19)") (class "Default")
      (node (ref "J14") (pin "19") (pinfunction "19_19") (pintype "passive"))
      (node (ref "J14") (pin "20") (pinfunction "20_20") (pintype "passive"))
    )
    (net (code "32") (name "Net-(J14-Pad21)") (class "Default")
      (node (ref "J14") (pin "21") (pinfunction "21_21") (pintype "passive"))
      (node (ref "J14") (pin "22") (pinfunction "22_22") (pintype "passive"))
    )
    (net (code "33") (name "Net-(J14-Pad23)") (class "Default")
      (node (ref "J14") (pin "23") (pinfunction "23_23") (pintype "passive"))
      (node (ref "J14") (pin "24") (pinfunction "24_24") (pintype "passive"))
    )
    (net (code "34") (name "Net-(J14-Pad25)") (class "Default")
      (node (ref "J14") (pin "25") (pinfunction "25_25") (pintype "passive"))
      (node (ref "J14") (pin "26") (pinfunction "26_26") (pintype "passive"))
    )
    (net (code "35") (name "Net-(J14-Pad27)") (class "Default")
      (node (ref "J14") (pin "27") (pinfunction "27_27") (pintype "passive"))
      (node (ref "J14") (pin "28") (pinfunction "28_28") (pintype "passive"))
    )
    (net (code "36") (name "Net-(J14-Pad29)") (class "Default")
      (node (ref "J14") (pin "29") (pinfunction "29_29") (pintype "passive"))
      (node (ref "J14") (pin "30") (pinfunction "30_30") (pintype "passive"))
    )
    (net (code "37") (name "Net-(J14-Pad31)") (class "Default")
      (node (ref "J14") (pin "31") (pinfunction "31_31") (pintype "passive"))
      (node (ref "J14") (pin "32") (pinfunction "32_32") (pintype "passive"))
    )
    (net (code "38") (name "Net-(J15-Pad3)") (class "Default")
      (node (ref "J15") (pin "3") (pinfunction "3_3") (pintype "passive"))
      (node (ref "J15") (pin "4") (pinfunction "4_4") (pintype "passive"))
    )
    (net (code "39") (name "Net-(J15-Pad7)") (class "Default")
      (node (ref "J15") (pin "7") (pinfunction "7_7") (pintype "passive"))
      (node (ref "J15") (pin "8") (pinfunction "8_8") (pintype "passive"))
    )
    (net (code "40") (name "Net-(J15-Pad10)") (class "Default")
      (node (ref "J15") (pin "10") (pinfunction "10_10") (pintype "passive"))
      (node (ref "J15") (pin "9") (pinfunction "9_9") (pintype "passive"))
    )
    (net (code "41") (name "Net-(J15-Pad11)") (class "Default")
      (node (ref "J15") (pin "11") (pinfunction "11_11") (pintype "passive"))
      (node (ref "J15") (pin "12") (pinfunction "12_12") (pintype "passive"))
    )
    (net (code "42") (name "Net-(J15-Pad13)") (class "Default")
      (node (ref "J15") (pin "13") (pinfunction "13_13") (pintype "passive"))
      (node (ref "J15") (pin "14") (pinfunction "14_14") (pintype "passive"))
    )
    (net (code "43") (name "Net-(J15-Pad15)") (class "Default")
      (node (ref "J15") (pin "15") (pinfunction "15_15") (pintype "passive"))
      (node (ref "J15") (pin "16") (pinfunction "16_16") (pintype "passive"))
    )
    (net (code "44") (name "Net-(J15-Pad17)") (class "Default")
      (node (ref "J15") (pin "17") (pinfunction "17_17") (pintype "passive"))
      (node (ref "J15") (pin "18") (pinfunction "18_18") (pintype "passive"))
    )
    (net (code "45") (name "Net-(J15-Pad19)") (class "Default")
      (node (ref "J15") (pin "19") (pinfunction "19_19") (pintype "passive"))
      (node (ref "J15") (pin "20") (pinfunction "20_20") (pintype "passive"))
    )
    (net (code "46") (name "Net-(R10-Pad1)") (class "Default")
      (node (ref "R10") (pin "1") (pinfunction "1_1") (pintype "passive"))
      (node (ref "SW1") (pin "1") (pinfunction "P1_1") (pintype "passive"))
      (node (ref "SW1") (pin "4") (pinfunction "P1_4") (pintype "passive"))
    )
    (net (code "47") (name "Net-(U1-VDDANA)") (class "Default")
      (node (ref "C12") (pin "2") (pinfunction "2_2") (pintype "passive"))
      (node (ref "FB") (pin "1") (pinfunction "1_1") (pintype "passive"))
      (node (ref "U1") (pin "6") (pinfunction "VDDANA_6") (pintype "power_in"))
    )
    (net (code "48") (name "Net-(U1-VDDCORE)") (class "Default")
      (node (ref "C10") (pin "2") (pinfunction "2_2") (pintype "passive"))
      (node (ref "U1") (pin "43") (pinfunction "VDDCORE_43") (pintype "power_in"))
    )
    (net (code "49") (name "Net-(U2-BST)") (class "Default")
      (node (ref "C4") (pin "1") (pinfunction "1_1") (pintype "passive"))
      (node (ref "U2") (pin "5") (pinfunction "BST_5") (pintype "bidirectional"))
    )
    (net (code "50") (name "Net-(U2-EN{slash}SYNC)") (class "Default")
      (node (ref "R1") (pin "1") (pinfunction "1_1") (pintype "passive"))
      (node (ref "U2") (pin "6") (pinfunction "EN/SYNC_6") (pintype "bidirectional"))
    )
    (net (code "51") (name "Net-(U2-FB)") (class "Default")
      (node (ref "C5") (pin "1") (pinfunction "1_1") (pintype "passive"))
      (node (ref "R2") (pin "2") (pinfunction "2_2") (pintype "passive"))
      (node (ref "R3") (pin "1") (pinfunction "1_1") (pintype "passive"))
      (node (ref "U2") (pin "8") (pinfunction "FB_8") (pintype "bidirectional"))
    )
    (net (code "52") (name "Net-(U2-SW)") (class "Default")
      (node (ref "C4") (pin "2") (pinfunction "2_2") (pintype "passive"))
      (node (ref "L1") (pin "1") (pinfunction "1_1") (pintype "passive"))
      (node (ref "U2") (pin "3") (pinfunction "SW_3") (pintype "bidirectional"))
    )
    (net (code "53") (name "Net-(U2-VCC)") (class "Default")
      (node (ref "C3") (pin "2") (pinfunction "2_2") (pintype "passive"))
      (node (ref "U2") (pin "7") (pinfunction "VCC_7") (pintype "bidirectional"))
    )
    (net (code "54") (name "Net-(U5-ILIM)") (class "Default")
      (node (ref "R7") (pin "1") (pinfunction "1_1") (pintype "passive"))
      (node (ref "U5") (pin "4") (pinfunction "ILIM_4") (pintype "input"))
    )
    (net (code "55") (name "Net-(U5-OUT1)") (class "Default")
      (node (ref "J2") (pin "2") (pinfunction "2_2") (pintype "passive"))
      (node (ref "U5") (pin "6") (pinfunction "OUT1_6") (pintype "output"))
    )
    (net (code "56") (name "Net-(U5-OUT2)") (class "Default")
      (node (ref "J2") (pin "1") (pinfunction "1_1") (pintype "passive"))
      (node (ref "U5") (pin "8") (pinfunction "OUT2_8") (pintype "output"))
    )
    (net (code "57") (name "Net-(U6-ILIM)") (class "Default")
      (node (ref "R8") (pin "1") (pinfunction "1_1") (pintype "passive"))
      (node (ref "U6") (pin "4") (pinfunction "ILIM_4") (pintype "input"))
    )
    (net (code "58") (name "Net-(U6-OUT1)") (class "Default")
      (node (ref "J3") (pin "2") (pinfunction "2_2") (pintype "passive"))
      (node (ref "U6") (pin "6") (pinfunction "OUT1_6") (pintype "output"))
    )
    (net (code "59") (name "Net-(U6-OUT2)") (class "Default")
      (node (ref "J3") (pin "1") (pinfunction "1_1") (pintype "passive"))
      (node (ref "U6") (pin "8") (pinfunction "OUT2_8") (pintype "output"))
    )
    (net (code "60") (name "Net-(U7-B2)") (class "Default")
      (node (ref "J8") (pin "1") (pinfunction "1_1") (pintype "passive"))
      (node (ref "U7") (pin "12") (pinfunction "B2_12") (pintype "bidirectional"))
    )
    (net (code "61") (name "Net-(U7-B3)") (class "Default")
      (node (ref "J9") (pin "1") (pinfunction "1_1") (pintype "passive"))
      (node (ref "U7") (pin "11") (pinfunction "B3_11") (pintype "bidirectional"))
    )
    (net (code "62") (name "Net-(U7-B4)") (class "Default")
      (node (ref "J10") (pin "1") (pinfunction "1_1") (pintype "passive"))
      (node (ref "U7") (pin "10") (pinfunction "B4_10") (pintype "bidirectional"))
    )
    (net (code "63") (name "RX") (class "Default")
      (node (ref "J17") (pin "P$3") (pinfunction "3_P$3") (pintype "passive"))
      (node (ref "U1") (pin "20") (pinfunction "PB11_20") (pintype "bidirectional"))
    )
    (net (code "64") (name "SCL1") (class "Default")
      (node (ref "J15") (pin "21") (pinfunction "21_21") (pintype "passive"))
      (node (ref "J15") (pin "22") (pinfunction "22_22") (pintype "passive"))
      (node (ref "J6") (pin "1") (pinfunction "1_1") (pintype "passive"))
      (node (ref "R13") (pin "2") (pinfunction "2_2") (pintype "passive"))
      (node (ref "U1") (pin "26") (pinfunction "PA17_26") (pintype "bidirectional"))
    )
    (net (code "65") (name "SCL2") (class "Default")
      (node (ref "J16") (pin "P$2") (pinfunction "2_P$2") (pintype "passive"))
      (node (ref "R15") (pin "2") (pinfunction "2_2") (pintype "passive"))
      (node (ref "U1") (pin "22") (pinfunction "PA13_22") (pintype "bidirectional"))
      (node (ref "U9") (pin "13") (pinfunction "AP_SCL/AP_SCLK_13") (pintype "input"))
    )
    (net (code "66") (name "SDA1") (class "Default")
      (node (ref "J15") (pin "23") (pinfunction "23_23") (pintype "passive"))
      (node (ref "J15") (pin "24") (pinfunction "24_24") (pintype "passive"))
      (node (ref "J6") (pin "2") (pinfunction "2_2") (pintype "passive"))
      (node (ref "R14") (pin "2") (pinfunction "2_2") (pintype "passive"))
      (node (ref "U1") (pin "25") (pinfunction "PA16_25") (pintype "bidirectional"))
    )
    (net (code "67") (name "SDA2") (class "Default")
      (node (ref "J16") (pin "P$3") (pinfunction "3_P$3") (pintype "passive"))
      (node (ref "R16") (pin "2") (pinfunction "2_2") (pintype "passive"))
      (node (ref "U1") (pin "21") (pinfunction "PA12_21") (pintype "bidirectional"))
      (node (ref "U9") (pin "14") (pinfunction "AP_SDA/AP_SDIO/AP_SDI_14") (pintype "bidirectional"))
    )
    (net (code "68") (name "SERVO1") (class "Default")
      (node (ref "J12") (pin "3") (pinfunction "3_3") (pintype "passive"))
      (node (ref "U1") (pin "1") (pinfunction "PA00_1") (pintype "bidirectional"))
    )
    (net (code "69") (name "SERVO2") (class "Default")
      (node (ref "J12") (pin "6") (pinfunction "6_6") (pintype "passive"))
      (node (ref "U1") (pin "2") (pinfunction "PA01_2") (pintype "bidirectional"))
    )
    (net (code "70") (name "SERVO3") (class "Default")
      (node (ref "J12") (pin "9") (pinfunction "9_9") (pintype "passive"))
      (node (ref "U1") (pin "13") (pinfunction "PA08_13") (pintype "bidirectional"))
    )
    (net (code "71") (name "SERVO4") (class "Default")
      (node (ref "J12") (pin "12") (pinfunction "12_12") (pintype "passive"))
      (node (ref "U1") (pin "14") (pinfunction "PA09_14") (pintype "bidirectional"))
    )
    (net (code "72") (name "SONAR1ECHO") (class "Default")
      (node (ref "U1") (pin "41") (pinfunction "PA28_41") (pintype "bidirectional"))
      (node (ref "U7") (pin "5") (pinfunction "A4_5") (pintype "bidirectional"))
    )
    (net (code "73") (name "SONAR1TRIG") (class "Default")
      (node (ref "J10") (pin "2") (pinfunction "2_2") (pintype "passive"))
      (node (ref "U1") (pin "39") (pinfunction "PA27_39") (pintype "bidirectional"))
    )
    (net (code "74") (name "SONAR2ECHO") (class "Default")
      (node (ref "U1") (pin "47") (pinfunction "PB02_47") (pintype "bidirectional"))
      (node (ref "U7") (pin "4") (pinfunction "A3_4") (pintype "bidirectional"))
    )
    (net (code "75") (name "SONAR2TRIG") (class "Default")
      (node (ref "J9") (pin "2") (pinfunction "2_2") (pintype "passive"))
      (node (ref "U1") (pin "38") (pinfunction "PB23_38") (pintype "bidirectional"))
    )
    (net (code "76") (name "SONAR3ECHO") (class "Default")
      (node (ref "U1") (pin "48") (pinfunction "PB03_48") (pintype "bidirectional"))
      (node (ref "U7") (pin "3") (pinfunction "A2_3") (pintype "bidirectional"))
    )
    (net (code "77") (name "SONAR3TRIG") (class "Default")
      (node (ref "J8") (pin "2") (pinfunction "2_2") (pintype "passive"))
      (node (ref "U1") (pin "37") (pinfunction "PB22_37") (pintype "bidirectional"))
    )
    (net (code "78") (name "SWCLK") (class "Default")
      (node (ref "R11") (pin "2") (pinfunction "2_2") (pintype "passive"))
      (node (ref "TP2") (pin "TP") (pinfunction "TP_TP") (pintype "input"))
      (node (ref "U1") (pin "45") (pinfunction "PA30_45") (pintype "bidirectional"))
    )
    (net (code "79") (name "SWDIO") (class "Default")
      (node (ref "TP3") (pin "TP") (pinfunction "TP_TP") (pintype "input"))
      (node (ref "U1") (pin "46") (pinfunction "PA31_46") (pintype "bidirectional"))
    )
    (net (code "80") (name "TX") (class "Default")
      (node (ref "J17") (pin "P$2") (pinfunction "2_P$2") (pintype "passive"))
      (node (ref "U1") (pin "19") (pinfunction "PB10_19") (pintype "bidirectional"))
    )
    (net (code "81") (name "VSENSE") (class "Default")
      (node (ref "R5") (pin "1") (pinfunction "1_1") (pintype "passive"))
      (node (ref "R6") (pin "1") (pinfunction "1_1") (pintype "passive"))
      (node (ref "U1") (pin "12") (pinfunction "PA07_12") (pintype "bidirectional"))
    )
    (net (code "82") (name "unconnected-(J15-Pad1)") (class "Default")
      (node (ref "J15") (pin "1") (pinfunction "1_1") (pintype "passive"))
    )
    (net (code "83") (name "unconnected-(J15-Pad5)") (class "Default")
      (node (ref "J15") (pin "5") (pinfunction "5_5") (pintype "passive"))
    )
    (net (code "84") (name "unconnected-(J17-4-PadP$4)") (class "Default")
      (node (ref "J17") (pin "P$4") (pinfunction "4_P$4") (pintype "passive"))
    )
    (net (code "85") (name "unconnected-(J17-5-PadP$5)") (class "Default")
      (node (ref "J17") (pin "P$5") (pinfunction "5_P$5") (pintype "passive"))
    )
    (net (code "86") (name "unconnected-(U1-PA03-Pad4)") (class "Default")
      (node (ref "U1") (pin "4") (pinfunction "PA03_4") (pintype "bidirectional"))
    )
    (net (code "87") (name "unconnected-(U1-PA11-Pad16)") (class "Default")
      (node (ref "U1") (pin "16") (pinfunction "PA11_16") (pintype "bidirectional"))
    )
    (net (code "88") (name "unconnected-(U7-A1-Pad2)") (class "Default")
      (node (ref "U7") (pin "2") (pinfunction "A1_2") (pintype "bidirectional"))
    )
    (net (code "89") (name "unconnected-(U7-B1-Pad13)") (class "Default")
      (node (ref "U7") (pin "13") (pinfunction "B1_13") (pintype "bidirectional"))
    )
    (net (code "90") (name "unconnected-(U7-NC-Pad9)") (class "Default")
      (node (ref "U7") (pin "9") (pinfunction "NC_9") (pintype "no_connect"))
    )
    (net (code "91") (name "unconnected-(U7-NC_2-Pad6)") (class "Default")
      (node (ref "U7") (pin "6") (pinfunction "NC_2_6") (pintype "no_connect"))
    )
    (net (code "92") (name "unconnected-(U9-INT1{slash}INT-Pad4)") (class "Default")
      (node (ref "U9") (pin "4") (pinfunction "INT1/INT_4") (pintype "output"))
    )
    (net (code "93") (name "unconnected-(U9-RESV_1-Pad2)") (class "Default")
      (node (ref "U9") (pin "2") (pinfunction "RESV_1_2") (pintype "bidirectional"))
    )
    (net (code "94") (name "unconnected-(U9-RESV_2-Pad3)") (class "Default")
      (node (ref "U9") (pin "3") (pinfunction "RESV_2_3") (pintype "bidirectional"))
    )
    (net (code "95") (name "unconnected-(U9-RESV_4-Pad10)") (class "Default")
      (node (ref "U9") (pin "10") (pinfunction "RESV_4_10") (pintype "bidirectional"))
    )
    (net (code "96") (name "unconnected-(U9-RESV_5-Pad11)") (class "Default")
      (node (ref "U9") (pin "11") (pinfunction "RESV_5_11") (pintype "bidirectional"))
    )
    (net (code "97") (name "unconnected-(USB1-ID-Pad4)") (class "Default")
      (node (ref "USB1") (pin "4") (pinfunction "ID_4") (pintype "bidirectional"))
    )
    (net (code "98") (name "unconnected-(USB1-VCC-Pad1)") (class "Default")
      (node (ref "USB1") (pin "1") (pinfunction "VCC_1") (pintype "bidirectional"))
    )
    (net (code "99") (name "~{RESET}") (class "Default")
      (node (ref "C14") (pin "1") (pinfunction "1_1") (pintype "passive"))
      (node (ref "J14") (pin "1") (pinfunction "1_1") (pintype "passive"))
      (node (ref "J14") (pin "2") (pinfunction "2_2") (pintype "passive"))
      (node (ref "R10") (pin "2") (pinfunction "2_2") (pintype "passive"))
      (node (ref "TP1") (pin "TP") (pinfunction "TP_TP") (pintype "input"))
      (node (ref "U1") (pin "40") (pinfunction "RSTN_40") (pintype "bidirectional"))
    )
  )
)
